# Spike_and_Hold_V2_1.net
KiCad netlist of a schematic drawn in Altium Designer
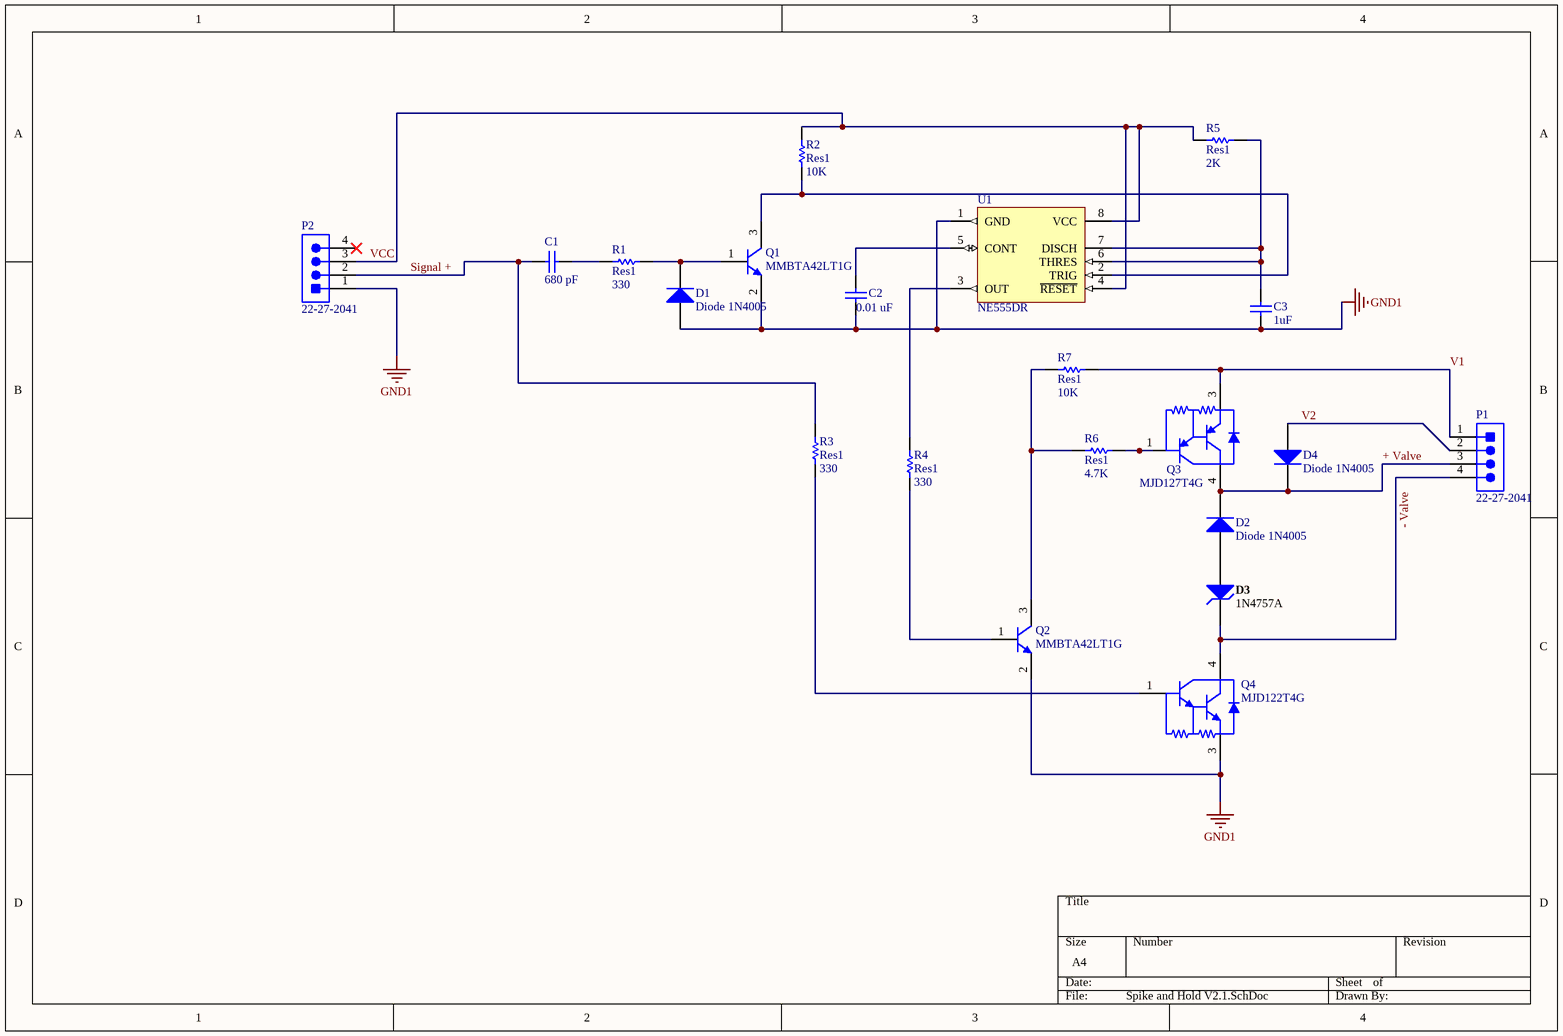
[diagram p0: Spike and Hold V2.1.SchDoc]

(export (version "E")
  (design (tool "Eeschema 10.0.6"))
  (components
    (comp (ref "C1")
      (value "680 pF")
      (footprint "CAPC1005X55X30LL05T10")
      (fields (field (name "PART NUMBER") "C0402C681K5RACTU") (field (name "MANUFACTURER") "Kemet"))
      (libsource (lib "Altium Content Vault") (part "CAP"))
    )
    (comp (ref "C2")
      (value "0.01 uF")
      (footprint "CAPC1608X87X35LL15T15")
      (fields (field (name "PART NUMBER") "C0603C103K5RACTU") (field (name "MANUFACTURER") "Kemet"))
      (libsource (lib "Altium Content Vault") (part "CMP-2006-03044-1"))
    )
    (comp (ref "C3")
      (value "1uF")
      (footprint "CAPC1206(3216)110_L")
      (description "CAP 1uF 50V ±10% 1206 (3216 Metric) Thickness 1.1mm SMD")
      (fields (field (name "TOLERANCE") "Â±10%"))
      (libsource (lib "Altium Content Vault") (part "CAP"))
    )
    (comp (ref "D1")
      (value "Diode 1N4005")
      (footprint "DO-41")
      (description "1 Amp General Purpose Rectifier")
      (fields (field (name "PUBLISHER") "Altium Limited"))
      (libsource (lib "Miscellaneous Devices") (part "Diode 1N4005"))
    )
    (comp (ref "D2")
      (value "Diode 1N4005")
      (footprint "DO-41")
      (description "1 Amp General Purpose Rectifier")
      (fields (field (name "PUBLISHER") "Altium Limited"))
      (libsource (lib "Miscellaneous Devices") (part "Diode 1N4005"))
    )
    (comp (ref "D3")
      (value "1N4757A")
      (footprint "FAIR-DO-41-2_V")
      (description "Zener Diode, 51V, 1W, 5%, -65 to 200 degC, 2-Pin DO-41, Body 2.72 x 5.2 mm, RoHS")
      (fields (field (name "MANUFACTURER") "Fairchild Semiconductor") (field (name "TOLERANCE") "5%"))
      (libsource (lib "Altium Content Vault") (part "FAIR-DZEN-A1K2-2"))
    )
    (comp (ref "D4")
      (value "Diode 1N4005")
      (footprint "DO-41")
      (description "1 Amp General Purpose Rectifier")
      (fields (field (name "PUBLISHER") "Altium Limited"))
      (libsource (lib "Miscellaneous Devices") (part "Diode 1N4005"))
    )
    (comp (ref "P1")
      (value "22-27-2041")
      (footprint "MOLX-22-27-2041_V")
      (description "Male Header, Pitch 2.54 mm, 1 x 4 Position, Height 11.7 mm, Tail Length 3.56 mm, RoHS, Bulk")
      (fields (field (name "MANUFACTURER") "Molex"))
      (libsource (lib "") (part "CN-1P-M-R4_1"))
    )
    (comp (ref "P2")
      (value "22-27-2041")
      (footprint "MOLX-22-27-2041_V")
      (description "Male Header, Pitch 2.54 mm, 1 x 4 Position, Height 11.7 mm, Tail Length 3.56 mm, RoHS, Bulk")
      (fields (field (name "MANUFACTURER") "Molex"))
      (libsource (lib "Altium Content Vault") (part "CN-1P-M-R4"))
    )
    (comp (ref "Q1")
      (value "MMBTA42LT1G")
      (footprint "ONSC-SOT-23-3-318-08_V")
      (description "High Voltage Transistor, NPN Silicon, 3-Pin SOT-23, Pb-Free, Tape and Reel")
      (fields (field (name "MANUFACTURER") "On Semiconductor"))
      (libsource (lib "Altium Content Vault") (part "CMP-1048-00662-1"))
    )
    (comp (ref "Q2")
      (value "MMBTA42LT1G")
      (footprint "ONSC-SOT-23-3-318-08_V")
      (description "High Voltage Transistor, NPN Silicon, 3-Pin SOT-23, Pb-Free, Tape and Reel")
      (fields (field (name "MANUFACTURER") "On Semiconductor"))
      (libsource (lib "Altium Content Vault") (part "CMP-1048-00662-1"))
    )
    (comp (ref "Q3")
      (value "MJD127T4G")
      (footprint "ONSC-DPAK-3-369C-01_V")
      (description "Complementary Darlington Power Transistor, 3-Pin DPAK, Pb-Free, Tape and Reel")
      (fields (field (name "MANUFACTURER") "On Semiconductor"))
      (libsource (lib "Altium Content Vault") (part "CMP-1047-00009-1"))
    )
    (comp (ref "Q4")
      (value "MJD122T4G")
      (footprint "ONSC-DPAK-3-369C-01_V")
      (description "Complementary Darlington Power Transistor, 3-Pin DPAK, Pb-Free, Tape and Reel")
      (fields (field (name "MANUFACTURER") "On Semiconductor"))
      (libsource (lib "Altium Content Vault") (part "CMP-1047-00007-1"))
    )
    (comp (ref "R1")
      (value "Res1")
      (footprint "AXIAL-0.3")
      (description "Resistor")
      (fields (field (name "ALTIUM_VALUE") "330") (field (name "PUBLISHER") "Altium Limited"))
      (libsource (lib "Miscellaneous Devices") (part "Res1"))
    )
    (comp (ref "R2")
      (value "Res1")
      (footprint "AXIAL-0.3")
      (description "Resistor")
      (fields (field (name "ALTIUM_VALUE") "10K") (field (name "PUBLISHER") "Altium Limited"))
      (libsource (lib "Miscellaneous Devices") (part "Res1"))
    )
    (comp (ref "R3")
      (value "Res1")
      (footprint "AXIAL-0.3")
      (description "Resistor")
      (fields (field (name "ALTIUM_VALUE") "330") (field (name "PUBLISHER") "Altium Limited"))
      (libsource (lib "Miscellaneous Devices") (part "Res1"))
    )
    (comp (ref "R4")
      (value "Res1")
      (footprint "AXIAL-0.3")
      (description "Resistor")
      (fields (field (name "ALTIUM_VALUE") "330") (field (name "PUBLISHER") "Altium Limited"))
      (libsource (lib "Miscellaneous Devices") (part "Res1"))
    )
    (comp (ref "R5")
      (value "Res1")
      (footprint "AXIAL-0.3")
      (description "Resistor")
      (fields (field (name "ALTIUM_VALUE") "2K") (field (name "PUBLISHER") "Altium Limited"))
      (libsource (lib "Miscellaneous Devices") (part "Res1"))
    )
    (comp (ref "R6")
      (value "Res1")
      (footprint "AXIAL-0.3")
      (description "Resistor")
      (fields (field (name "ALTIUM_VALUE") "4.7K") (field (name "PUBLISHER") "Altium Limited"))
      (libsource (lib "Miscellaneous Devices") (part "Res1"))
    )
    (comp (ref "R7")
      (value "Res1")
      (footprint "AXIAL-0.3")
      (description "Resistor")
      (fields (field (name "ALTIUM_VALUE") "10K") (field (name "PUBLISHER") "Altium Limited"))
      (libsource (lib "Miscellaneous Devices") (part "Res1"))
    )
    (comp (ref "U1")
      (value "NE555DR")
      (footprint "D0008A_L")
      (libsource (lib "Altium Content Vault") (part "CMP-1685-00007-1"))
    )
  )
  (nets
    (net (code "1") (name "/+ Valve") (class "Default")
      (node (ref "D2") (pin "2") (pinfunction "K_2") (pintype "passive"))
      (node (ref "D4") (pin "2") (pinfunction "K_2") (pintype "passive"))
      (node (ref "P1") (pin "3") (pinfunction "3_3") (pintype "passive"))
      (node (ref "Q3") (pin "4") (pinfunction "C_4") (pintype "passive"))
    )
    (net (code "2") (name "/- Valve") (class "Default")
      (node (ref "D3") (pin "2") (pinfunction "K_2") (pintype "passive"))
      (node (ref "P1") (pin "4") (pinfunction "4_4") (pintype "passive"))
      (node (ref "Q4") (pin "4") (pinfunction "C_4") (pintype "passive"))
    )
    (net (code "3") (name "/Signal +") (class "Default")
      (node (ref "C1") (pin "1") (pinfunction "1_1") (pintype "passive"))
      (node (ref "P2") (pin "2") (pinfunction "2_2") (pintype "passive"))
      (node (ref "R3") (pin "2") (pinfunction "2_2") (pintype "passive"))
    )
    (net (code "4") (name "/V1") (class "Default")
      (node (ref "P1") (pin "1") (pinfunction "1_1") (pintype "passive"))
      (node (ref "Q3") (pin "3") (pinfunction "E_3") (pintype "passive"))
      (node (ref "R7") (pin "2") (pinfunction "2_2") (pintype "passive"))
    )
    (net (code "5") (name "/V2") (class "Default")
      (node (ref "D4") (pin "1") (pinfunction "A_1") (pintype "passive"))
      (node (ref "P1") (pin "2") (pinfunction "2_2") (pintype "passive"))
    )
    (net (code "6") (name "/VCC") (class "Default")
      (node (ref "P2") (pin "3") (pinfunction "3_3") (pintype "passive"))
      (node (ref "R2") (pin "2") (pinfunction "2_2") (pintype "passive"))
      (node (ref "R5") (pin "1") (pinfunction "1_1") (pintype "passive"))
      (node (ref "U1") (pin "4") (pinfunction "~{RESET}_4") (pintype "input"))
      (node (ref "U1") (pin "8") (pinfunction "VCC_8") (pintype "power_in"))
    )
    (net (code "7") (name "GND1") (class "Default")
      (node (ref "C2") (pin "1") (pinfunction "1_1") (pintype "passive"))
      (node (ref "C3") (pin "1") (pinfunction "1_1") (pintype "passive"))
      (node (ref "D1") (pin "1") (pinfunction "A_1") (pintype "passive"))
      (node (ref "P2") (pin "1") (pinfunction "1_1") (pintype "passive"))
      (node (ref "Q1") (pin "2") (pinfunction "E_2") (pintype "passive"))
      (node (ref "Q2") (pin "2") (pinfunction "E_2") (pintype "passive"))
      (node (ref "Q4") (pin "3") (pinfunction "E_3") (pintype "passive"))
      (node (ref "U1") (pin "1") (pinfunction "GND_1") (pintype "output"))
    )
    (net (code "8") (name "Net-(C1-Pad2)") (class "Default")
      (node (ref "C1") (pin "2") (pinfunction "2_2") (pintype "passive"))
      (node (ref "R1") (pin "1") (pinfunction "1_1") (pintype "passive"))
    )
    (net (code "9") (name "Net-(D1-K)") (class "Default")
      (node (ref "D1") (pin "2") (pinfunction "K_2") (pintype "passive"))
      (node (ref "Q1") (pin "1") (pinfunction "B_1") (pintype "passive"))
      (node (ref "R1") (pin "2") (pinfunction "2_2") (pintype "passive"))
    )
    (net (code "10") (name "Net-(D2-A)") (class "Default")
      (node (ref "D2") (pin "1") (pinfunction "A_1") (pintype "passive"))
      (node (ref "D3") (pin "1") (pinfunction "A_1") (pintype "passive"))
    )
    (net (code "11") (name "Net-(Q1-C)") (class "Default")
      (node (ref "Q1") (pin "3") (pinfunction "C_3") (pintype "passive"))
      (node (ref "R2") (pin "1") (pinfunction "1_1") (pintype "passive"))
      (node (ref "U1") (pin "2") (pinfunction "TRIG_2") (pintype "input"))
    )
    (net (code "12") (name "Net-(Q2-B)") (class "Default")
      (node (ref "Q2") (pin "1") (pinfunction "B_1") (pintype "passive"))
      (node (ref "R4") (pin "1") (pinfunction "1_1") (pintype "passive"))
    )
    (net (code "13") (name "Net-(Q2-C)") (class "Default")
      (node (ref "Q2") (pin "3") (pinfunction "C_3") (pintype "passive"))
      (node (ref "R6") (pin "1") (pinfunction "1_1") (pintype "passive"))
      (node (ref "R7") (pin "1") (pinfunction "1_1") (pintype "passive"))
    )
    (net (code "14") (name "Net-(Q3-B)") (class "Default")
      (node (ref "Q3") (pin "1") (pinfunction "B_1") (pintype "passive"))
      (node (ref "R6") (pin "2") (pinfunction "2_2") (pintype "passive"))
    )
    (net (code "15") (name "Net-(Q4-B)") (class "Default")
      (node (ref "Q4") (pin "1") (pinfunction "B_1") (pintype "passive"))
      (node (ref "R3") (pin "1") (pinfunction "1_1") (pintype "passive"))
    )
    (net (code "16") (name "Net-(U1-CONT)") (class "Default")
      (node (ref "C2") (pin "2") (pinfunction "2_2") (pintype "passive"))
      (node (ref "U1") (pin "5") (pinfunction "CONT_5") (pintype "bidirectional"))
    )
    (net (code "17") (name "Net-(U1-DISCH)") (class "Default")
      (node (ref "C3") (pin "2") (pinfunction "2_2") (pintype "passive"))
      (node (ref "R5") (pin "2") (pinfunction "2_2") (pintype "passive"))
      (node (ref "U1") (pin "6") (pinfunction "THRES_6") (pintype "input"))
      (node (ref "U1") (pin "7") (pinfunction "DISCH_7") (pintype "open_collector"))
    )
    (net (code "18") (name "Net-(U1-OUT)") (class "Default")
      (node (ref "R4") (pin "2") (pinfunction "2_2") (pintype "passive"))
      (node (ref "U1") (pin "3") (pinfunction "OUT_3") (pintype "output"))
    )
    (net (code "19") (name "unconnected-(P2-Pad4)") (class "Default")
      (node (ref "P2") (pin "4") (pinfunction "4_4") (pintype "passive+no_connect"))
    )
  )
)
